# Prototype.net
KiCad netlist of a schematic drawn in EAGLE
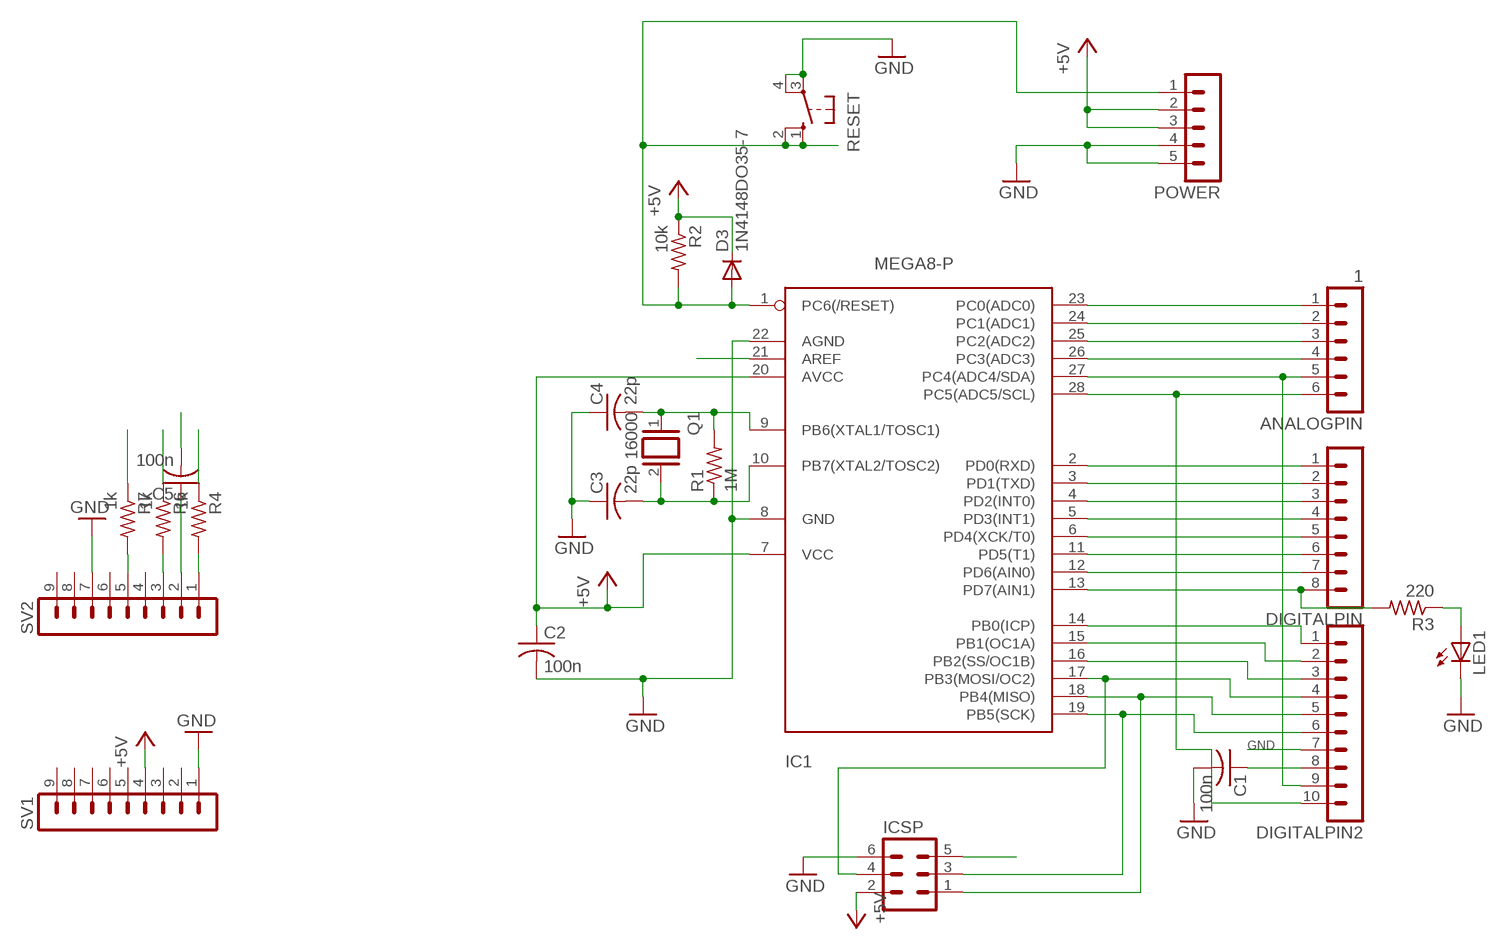
[diagram p0: schematic, sheet 1]

(export (version "E")
  (design (tool "Eeschema 10.0.6"))
  (components
    (comp (ref "ANALOGPIN")
      (value "1")
      (footprint "eagle-import:MA06-1")
      (libsource (lib "eagle-import") (part "MA06-1"))
    )
    (comp (ref "C1")
      (value "100n")
      (footprint "eagle-import:C025-024X044")
      (libsource (lib "eagle-import") (part "C-US025-024X044"))
    )
    (comp (ref "C2")
      (value "100n")
      (footprint "eagle-import:C025-024X044")
      (libsource (lib "eagle-import") (part "C-US025-024X044"))
    )
    (comp (ref "C3")
      (value "22p")
      (footprint "eagle-import:C025-024X044")
      (libsource (lib "eagle-import") (part "C-US025-024X044"))
    )
    (comp (ref "C4")
      (value "22p")
      (footprint "eagle-import:C025-024X044")
      (libsource (lib "eagle-import") (part "C-US025-024X044"))
    )
    (comp (ref "C5")
      (value "100n")
      (footprint "eagle-import:C025-024X044")
      (libsource (lib "eagle-import") (part "C-US025-024X044"))
    )
    (comp (ref "D3")
      (value "1N4148DO35-7")
      (footprint "eagle-import:DO35-7")
      (libsource (lib "eagle-import") (part "1N4148DO35-7"))
    )
    (comp (ref "DIGITALPIN")
      (value "MA08-1")
      (footprint "eagle-import:MA08-1")
      (libsource (lib "eagle-import") (part "MA08-1"))
    )
    (comp (ref "DIGITALPIN2")
      (value "MA10-1")
      (footprint "eagle-import:MA10-1")
      (libsource (lib "eagle-import") (part "MA10-1"))
    )
    (comp (ref "IC1")
      (value "MEGA8-P")
      (footprint "eagle-import:DIL28-3")
      (libsource (lib "eagle-import") (part "MEGA8-P"))
    )
    (comp (ref "ICSP")
      (value "MA03-2")
      (footprint "eagle-import:MA03-2")
      (libsource (lib "eagle-import") (part "MA03-2"))
    )
    (comp (ref "LED1")
      (value "LED3MM")
      (footprint "eagle-import:LED3MM")
      (libsource (lib "eagle-import") (part "LED3MM"))
    )
    (comp (ref "POWER")
      (value "MA05-1")
      (footprint "eagle-import:MA05-1")
      (libsource (lib "eagle-import") (part "MA05-1"))
    )
    (comp (ref "Q1")
      (value "16000")
      (footprint "eagle-import:QS")
      (libsource (lib "eagle-import") (part "XTAL/S"))
    )
    (comp (ref "R1")
      (value "1M")
      (footprint "eagle-import:0204_7")
      (libsource (lib "eagle-import") (part "R-US_0204/7"))
    )
    (comp (ref "R2")
      (value "10k")
      (footprint "eagle-import:0204_7")
      (libsource (lib "eagle-import") (part "R-US_0204/7"))
    )
    (comp (ref "R3")
      (value "220")
      (footprint "eagle-import:0204_7")
      (libsource (lib "eagle-import") (part "R-US_0204/7"))
    )
    (comp (ref "R4")
      (value "1k")
      (footprint "eagle-import:0204_7")
      (libsource (lib "eagle-import") (part "R-US_0204/7"))
    )
    (comp (ref "R6")
      (value "1k")
      (footprint "eagle-import:0204_7")
      (libsource (lib "eagle-import") (part "R-US_0204/7"))
    )
    (comp (ref "R7")
      (value "1k")
      (footprint "eagle-import:0204_7")
      (libsource (lib "eagle-import") (part "R-US_0204/7"))
    )
    (comp (ref "RESET")
      (value "10-XX")
      (footprint "eagle-import:B3F-10XX")
      (libsource (lib "eagle-import") (part "10-XX"))
    )
    (comp (ref "SV1")
      (value "MA09-1")
      (footprint "eagle-import:MA09-1")
      (libsource (lib "eagle-import") (part "MA09-1"))
    )
    (comp (ref "SV2")
      (value "MA09-1")
      (footprint "eagle-import:MA09-1")
      (libsource (lib "eagle-import") (part "MA09-1"))
    )
  )
  (nets
    (net (code "1") (name "+5V") (class "Default")
      (node (ref "C2") (pin "1") (pinfunction "1_1") (pintype "passive"))
      (node (ref "D3") (pin "C") (pinfunction "C_C") (pintype "passive"))
      (node (ref "IC1") (pin "20") (pinfunction "AVCC_20") (pintype "power_in"))
      (node (ref "IC1") (pin "7") (pinfunction "VCC_7") (pintype "power_in"))
      (node (ref "ICSP") (pin "2") (pinfunction "2_2") (pintype "passive"))
      (node (ref "POWER") (pin "2") (pinfunction "2_2") (pintype "passive"))
      (node (ref "POWER") (pin "3") (pinfunction "3_3") (pintype "passive"))
      (node (ref "R2") (pin "1") (pinfunction "1_1") (pintype "passive"))
      (node (ref "SV1") (pin "4") (pinfunction "4_4") (pintype "passive"))
    )
    (net (code "2") (name "/AREF") (class "Default")
      (node (ref "C1") (pin "1") (pinfunction "1_1") (pintype "passive"))
      (node (ref "DIGITALPIN2") (pin "8") (pinfunction "8_8") (pintype "passive"))
      (node (ref "IC1") (pin "21") (pinfunction "AREF_21") (pintype "passive"))
    )
    (net (code "3") (name "/RES1") (class "Default")
      (node (ref "C5") (pin "2") (pinfunction "2_2") (pintype "passive"))
      (node (ref "D3") (pin "A") (pinfunction "A_A") (pintype "passive"))
      (node (ref "IC1") (pin "1") (pinfunction "PC6(/RESET)_1") (pintype "bidirectional"))
      (node (ref "ICSP") (pin "5") (pinfunction "5_5") (pintype "passive"))
      (node (ref "POWER") (pin "1") (pinfunction "1_1") (pintype "passive"))
      (node (ref "R2") (pin "2") (pinfunction "2_2") (pintype "passive"))
      (node (ref "R6") (pin "1") (pinfunction "1_1") (pintype "passive"))
      (node (ref "RESET") (pin "1") (pinfunction "S_1") (pintype "passive"))
      (node (ref "RESET") (pin "2") (pinfunction "S1_2") (pintype "passive"))
    )
    (net (code "4") (name "/RXD") (class "Default")
      (node (ref "DIGITALPIN") (pin "1") (pinfunction "1_1") (pintype "passive"))
      (node (ref "IC1") (pin "2") (pinfunction "PD0(RXD)_2") (pintype "bidirectional"))
      (node (ref "R7") (pin "1") (pinfunction "1_1") (pintype "passive"))
    )
    (net (code "5") (name "/TXD") (class "Default")
      (node (ref "DIGITALPIN") (pin "2") (pinfunction "2_2") (pintype "passive"))
      (node (ref "IC1") (pin "3") (pinfunction "PD1(TXD)_3") (pintype "bidirectional"))
      (node (ref "R4") (pin "1") (pinfunction "1_1") (pintype "passive"))
    )
    (net (code "6") (name "GND") (class "Default")
      (node (ref "C1") (pin "2") (pinfunction "2_2") (pintype "passive"))
      (node (ref "C2") (pin "2") (pinfunction "2_2") (pintype "passive"))
      (node (ref "C3") (pin "1") (pinfunction "1_1") (pintype "passive"))
      (node (ref "C4") (pin "1") (pinfunction "1_1") (pintype "passive"))
      (node (ref "DIGITALPIN2") (pin "7") (pinfunction "7_7") (pintype "passive"))
      (node (ref "IC1") (pin "22") (pinfunction "AGND_22") (pintype "power_in"))
      (node (ref "IC1") (pin "8") (pinfunction "GND_8") (pintype "power_in"))
      (node (ref "ICSP") (pin "6") (pinfunction "6_6") (pintype "passive"))
      (node (ref "LED1") (pin "K") (pinfunction "C_K") (pintype "passive"))
      (node (ref "POWER") (pin "4") (pinfunction "4_4") (pintype "passive"))
      (node (ref "POWER") (pin "5") (pinfunction "5_5") (pintype "passive"))
      (node (ref "RESET") (pin "3") (pinfunction "P_3") (pintype "passive"))
      (node (ref "RESET") (pin "4") (pinfunction "P1_4") (pintype "passive"))
      (node (ref "SV1") (pin "1") (pinfunction "1_1") (pintype "passive"))
      (node (ref "SV2") (pin "7") (pinfunction "7_7") (pintype "passive"))
    )
    (net (code "7") (name "Net-(C5-Pad1)") (class "Default")
      (node (ref "C5") (pin "1") (pinfunction "1_1") (pintype "passive"))
      (node (ref "SV2") (pin "2") (pinfunction "2_2") (pintype "passive"))
    )
    (net (code "8") (name "Net-(IC1-PB0(ICP))") (class "Default")
      (node (ref "DIGITALPIN2") (pin "1") (pinfunction "1_1") (pintype "passive"))
      (node (ref "IC1") (pin "14") (pinfunction "PB0(ICP)_14") (pintype "bidirectional"))
    )
    (net (code "9") (name "Net-(IC1-PB1(OC1A))") (class "Default")
      (node (ref "DIGITALPIN2") (pin "2") (pinfunction "2_2") (pintype "passive"))
      (node (ref "IC1") (pin "15") (pinfunction "PB1(OC1A)_15") (pintype "bidirectional"))
    )
    (net (code "10") (name "Net-(IC1-PB2(SS{slash}OC1B))") (class "Default")
      (node (ref "DIGITALPIN2") (pin "3") (pinfunction "3_3") (pintype "passive"))
      (node (ref "IC1") (pin "16") (pinfunction "PB2(SS/OC1B)_16") (pintype "bidirectional"))
    )
    (net (code "11") (name "Net-(IC1-PB3(MOSI{slash}OC2))") (class "Default")
      (node (ref "DIGITALPIN2") (pin "4") (pinfunction "4_4") (pintype "passive"))
      (node (ref "IC1") (pin "17") (pinfunction "PB3(MOSI/OC2)_17") (pintype "bidirectional"))
      (node (ref "ICSP") (pin "4") (pinfunction "4_4") (pintype "passive"))
    )
    (net (code "12") (name "Net-(IC1-PB4(MISO))") (class "Default")
      (node (ref "DIGITALPIN2") (pin "5") (pinfunction "5_5") (pintype "passive"))
      (node (ref "IC1") (pin "18") (pinfunction "PB4(MISO)_18") (pintype "bidirectional"))
      (node (ref "ICSP") (pin "1") (pinfunction "1_1") (pintype "passive"))
    )
    (net (code "13") (name "Net-(IC1-PB5(SCK))") (class "Default")
      (node (ref "DIGITALPIN2") (pin "6") (pinfunction "6_6") (pintype "passive"))
      (node (ref "IC1") (pin "19") (pinfunction "PB5(SCK)_19") (pintype "bidirectional"))
      (node (ref "ICSP") (pin "3") (pinfunction "3_3") (pintype "passive"))
    )
    (net (code "14") (name "Net-(IC1-PB6(XTAL1{slash}TOSC1))") (class "Default")
      (node (ref "C4") (pin "2") (pinfunction "2_2") (pintype "passive"))
      (node (ref "IC1") (pin "9") (pinfunction "PB6(XTAL1/TOSC1)_9") (pintype "bidirectional"))
      (node (ref "Q1") (pin "1") (pinfunction "1_1") (pintype "passive"))
      (node (ref "R1") (pin "2") (pinfunction "2_2") (pintype "passive"))
    )
    (net (code "15") (name "Net-(IC1-PB7(XTAL2{slash}TOSC2))") (class "Default")
      (node (ref "C3") (pin "2") (pinfunction "2_2") (pintype "passive"))
      (node (ref "IC1") (pin "10") (pinfunction "PB7(XTAL2/TOSC2)_10") (pintype "bidirectional"))
      (node (ref "Q1") (pin "2") (pinfunction "2_2") (pintype "passive"))
      (node (ref "R1") (pin "1") (pinfunction "1_1") (pintype "passive"))
    )
    (net (code "16") (name "Net-(IC1-PC0(ADC0))") (class "Default")
      (node (ref "ANALOGPIN") (pin "1") (pinfunction "1_1") (pintype "passive"))
      (node (ref "IC1") (pin "23") (pinfunction "PC0(ADC0)_23") (pintype "bidirectional"))
    )
    (net (code "17") (name "Net-(IC1-PC1(ADC1))") (class "Default")
      (node (ref "ANALOGPIN") (pin "2") (pinfunction "2_2") (pintype "passive"))
      (node (ref "IC1") (pin "24") (pinfunction "PC1(ADC1)_24") (pintype "bidirectional"))
    )
    (net (code "18") (name "Net-(IC1-PC2(ADC2))") (class "Default")
      (node (ref "ANALOGPIN") (pin "3") (pinfunction "3_3") (pintype "passive"))
      (node (ref "IC1") (pin "25") (pinfunction "PC2(ADC2)_25") (pintype "bidirectional"))
    )
    (net (code "19") (name "Net-(IC1-PC3(ADC3))") (class "Default")
      (node (ref "ANALOGPIN") (pin "4") (pinfunction "4_4") (pintype "passive"))
      (node (ref "IC1") (pin "26") (pinfunction "PC3(ADC3)_26") (pintype "bidirectional"))
    )
    (net (code "20") (name "Net-(IC1-PC4(ADC4{slash}SDA))") (class "Default")
      (node (ref "ANALOGPIN") (pin "5") (pinfunction "5_5") (pintype "passive"))
      (node (ref "DIGITALPIN2") (pin "9") (pinfunction "9_9") (pintype "passive"))
      (node (ref "IC1") (pin "27") (pinfunction "PC4(ADC4/SDA)_27") (pintype "bidirectional"))
    )
    (net (code "21") (name "Net-(IC1-PC5(ADC5{slash}SCL))") (class "Default")
      (node (ref "ANALOGPIN") (pin "6") (pinfunction "6_6") (pintype "passive"))
      (node (ref "DIGITALPIN2") (pin "10") (pinfunction "10_10") (pintype "passive"))
      (node (ref "IC1") (pin "28") (pinfunction "PC5(ADC5/SCL)_28") (pintype "bidirectional"))
    )
    (net (code "22") (name "Net-(IC1-PD2(INT0))") (class "Default")
      (node (ref "DIGITALPIN") (pin "3") (pinfunction "3_3") (pintype "passive"))
      (node (ref "IC1") (pin "4") (pinfunction "PD2(INT0)_4") (pintype "bidirectional"))
    )
    (net (code "23") (name "Net-(IC1-PD3(INT1))") (class "Default")
      (node (ref "DIGITALPIN") (pin "4") (pinfunction "4_4") (pintype "passive"))
      (node (ref "IC1") (pin "5") (pinfunction "PD3(INT1)_5") (pintype "bidirectional"))
    )
    (net (code "24") (name "Net-(IC1-PD4(XCK{slash}T0))") (class "Default")
      (node (ref "DIGITALPIN") (pin "5") (pinfunction "5_5") (pintype "passive"))
      (node (ref "IC1") (pin "6") (pinfunction "PD4(XCK/T0)_6") (pintype "bidirectional"))
    )
    (net (code "25") (name "Net-(IC1-PD5(T1))") (class "Default")
      (node (ref "DIGITALPIN") (pin "6") (pinfunction "6_6") (pintype "passive"))
      (node (ref "IC1") (pin "11") (pinfunction "PD5(T1)_11") (pintype "bidirectional"))
    )
    (net (code "26") (name "Net-(IC1-PD6(AIN0))") (class "Default")
      (node (ref "DIGITALPIN") (pin "7") (pinfunction "7_7") (pintype "passive"))
      (node (ref "IC1") (pin "12") (pinfunction "PD6(AIN0)_12") (pintype "bidirectional"))
    )
    (net (code "27") (name "Net-(IC1-PD7(AIN1))") (class "Default")
      (node (ref "DIGITALPIN") (pin "8") (pinfunction "8_8") (pintype "passive"))
      (node (ref "IC1") (pin "13") (pinfunction "PD7(AIN1)_13") (pintype "bidirectional"))
      (node (ref "R3") (pin "2") (pinfunction "2_2") (pintype "passive"))
    )
    (net (code "28") (name "Net-(LED1-PadA)") (class "Default")
      (node (ref "LED1") (pin "A") (pinfunction "A_A") (pintype "passive"))
      (node (ref "R3") (pin "1") (pinfunction "1_1") (pintype "passive"))
    )
    (net (code "29") (name "Net-(R4-Pad2)") (class "Default")
      (node (ref "R4") (pin "2") (pinfunction "2_2") (pintype "passive"))
      (node (ref "SV2") (pin "1") (pinfunction "1_1") (pintype "passive"))
    )
    (net (code "30") (name "Net-(R6-Pad2)") (class "Default")
      (node (ref "R6") (pin "2") (pinfunction "2_2") (pintype "passive"))
      (node (ref "SV2") (pin "3") (pinfunction "3_3") (pintype "passive"))
    )
    (net (code "31") (name "Net-(R7-Pad2)") (class "Default")
      (node (ref "R7") (pin "2") (pinfunction "2_2") (pintype "passive"))
      (node (ref "SV2") (pin "5") (pinfunction "5_5") (pintype "passive"))
    )
    (net (code "32") (name "unconnected-(SV1-Pad2)") (class "Default")
      (node (ref "SV1") (pin "2") (pinfunction "2_2") (pintype "passive"))
    )
    (net (code "33") (name "unconnected-(SV1-Pad3)") (class "Default")
      (node (ref "SV1") (pin "3") (pinfunction "3_3") (pintype "passive"))
    )
    (net (code "34") (name "unconnected-(SV1-Pad5)") (class "Default")
      (node (ref "SV1") (pin "5") (pinfunction "5_5") (pintype "passive"))
    )
    (net (code "35") (name "unconnected-(SV1-Pad6)") (class "Default")
      (node (ref "SV1") (pin "6") (pinfunction "6_6") (pintype "passive"))
    )
    (net (code "36") (name "unconnected-(SV1-Pad7)") (class "Default")
      (node (ref "SV1") (pin "7") (pinfunction "7_7") (pintype "passive"))
    )
    (net (code "37") (name "unconnected-(SV1-Pad8)") (class "Default")
      (node (ref "SV1") (pin "8") (pinfunction "8_8") (pintype "passive"))
    )
    (net (code "38") (name "unconnected-(SV1-Pad9)") (class "Default")
      (node (ref "SV1") (pin "9") (pinfunction "9_9") (pintype "passive"))
    )
    (net (code "39") (name "unconnected-(SV2-Pad4)") (class "Default")
      (node (ref "SV2") (pin "4") (pinfunction "4_4") (pintype "passive"))
    )
    (net (code "40") (name "unconnected-(SV2-Pad6)") (class "Default")
      (node (ref "SV2") (pin "6") (pinfunction "6_6") (pintype "passive"))
    )
    (net (code "41") (name "unconnected-(SV2-Pad8)") (class "Default")
      (node (ref "SV2") (pin "8") (pinfunction "8_8") (pintype "passive"))
    )
    (net (code "42") (name "unconnected-(SV2-Pad9)") (class "Default")
      (node (ref "SV2") (pin "9") (pinfunction "9_9") (pintype "passive"))
    )
  )
)
